# firefly-instrument-controller.net
KiCad netlist of a schematic drawn in EAGLE
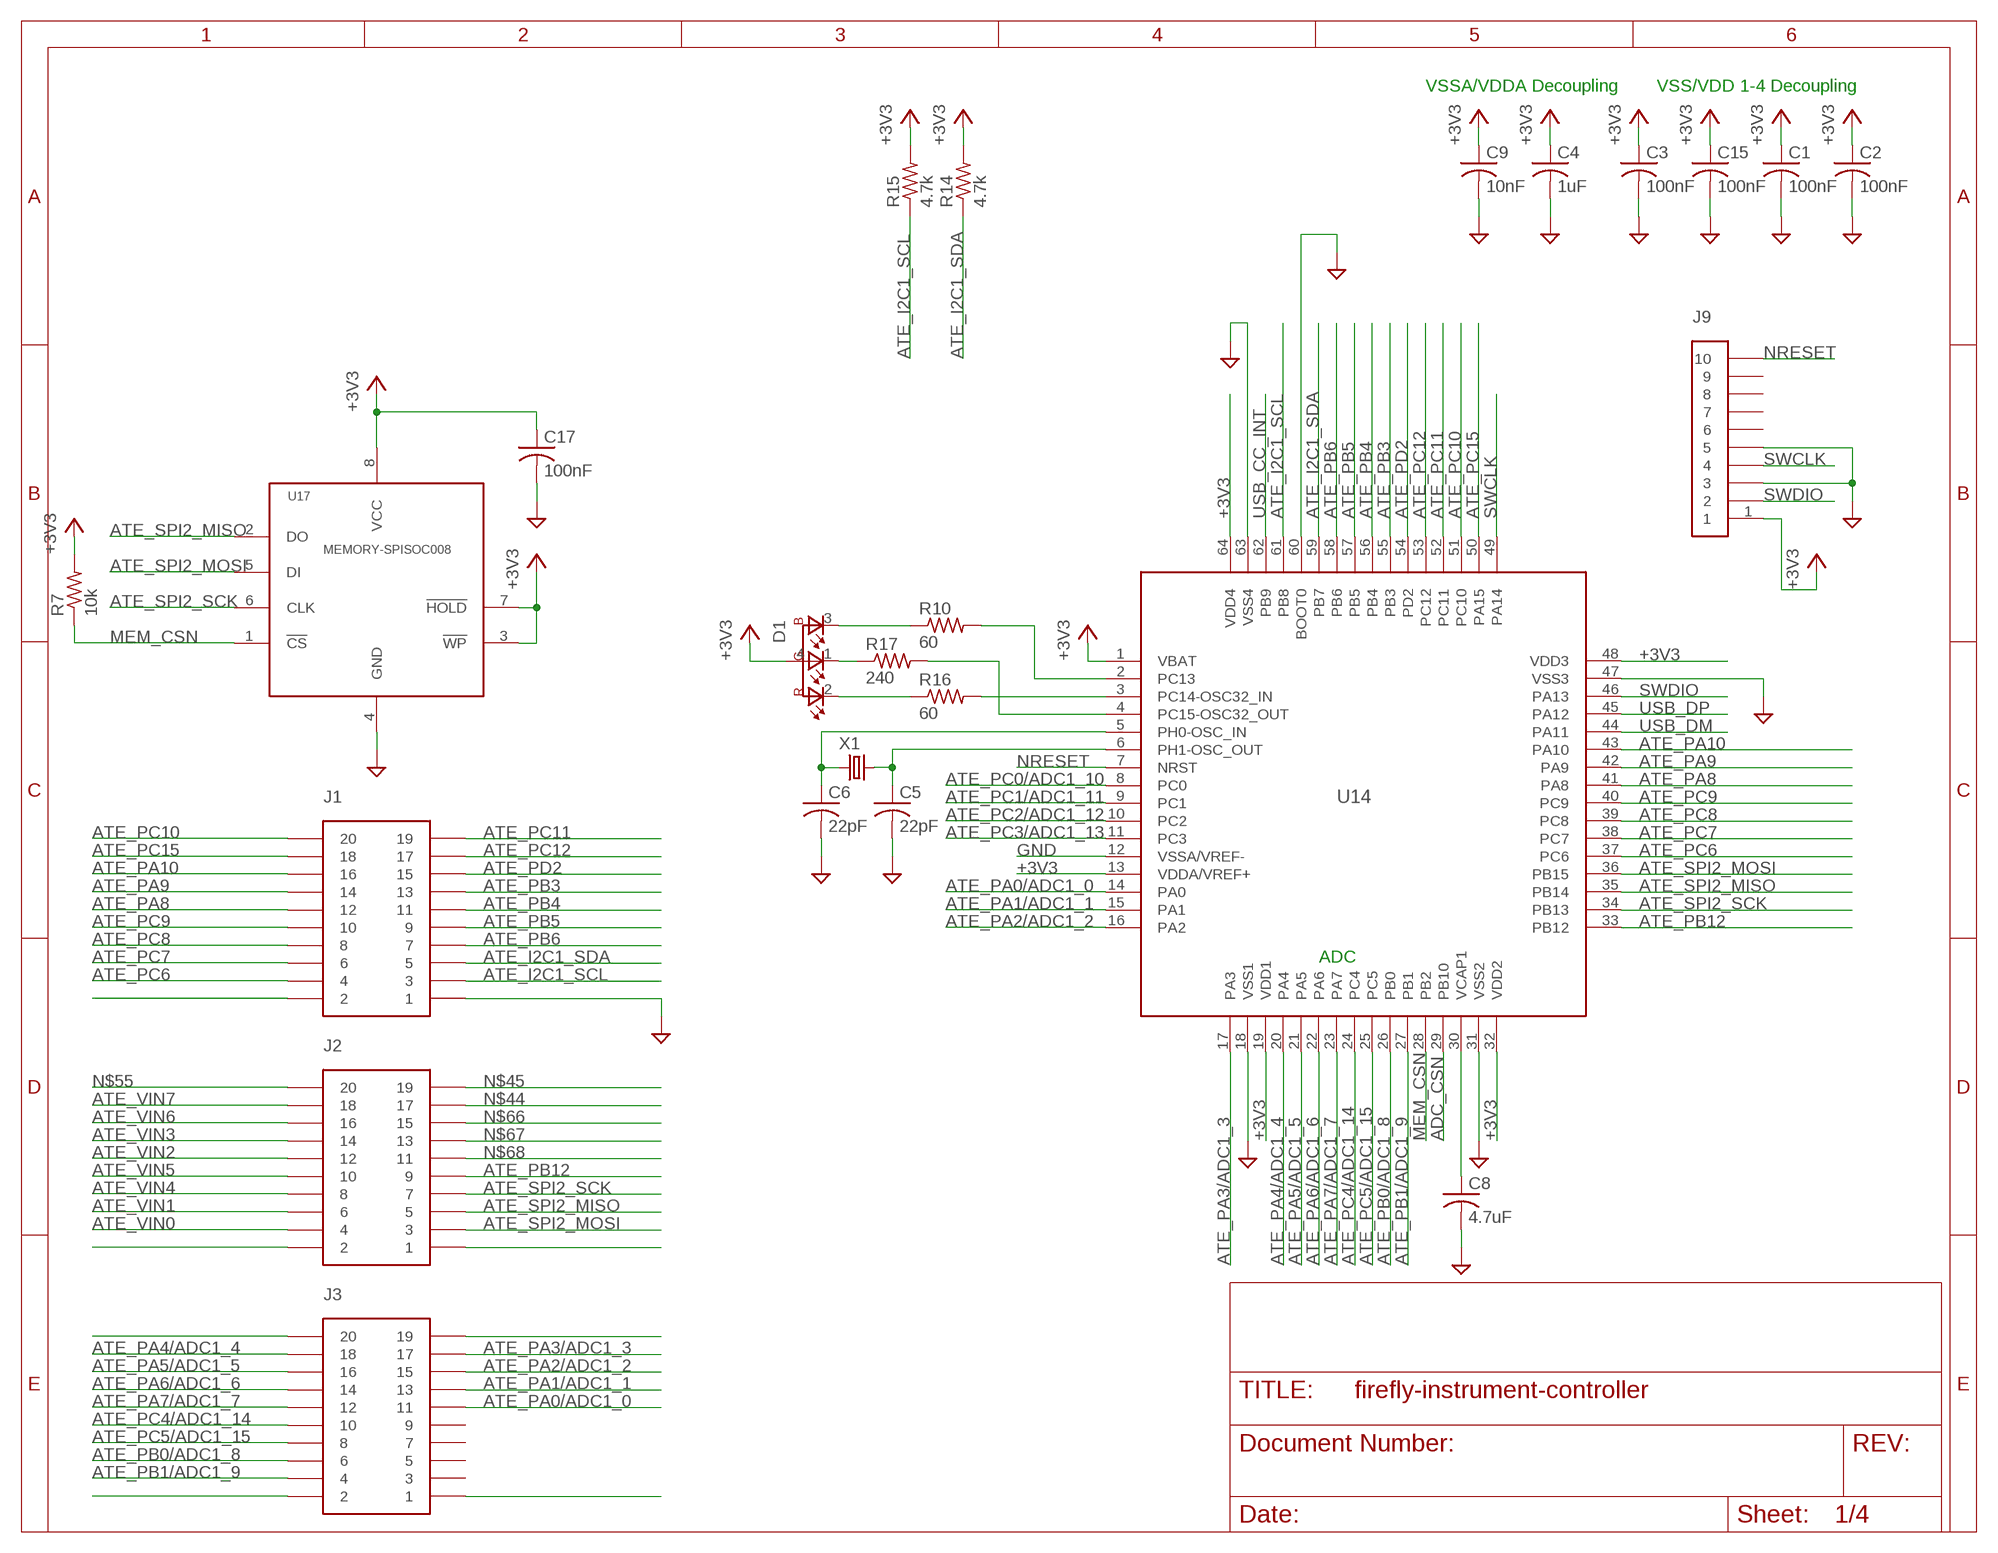
[diagram p0: schematic, sheet 1]
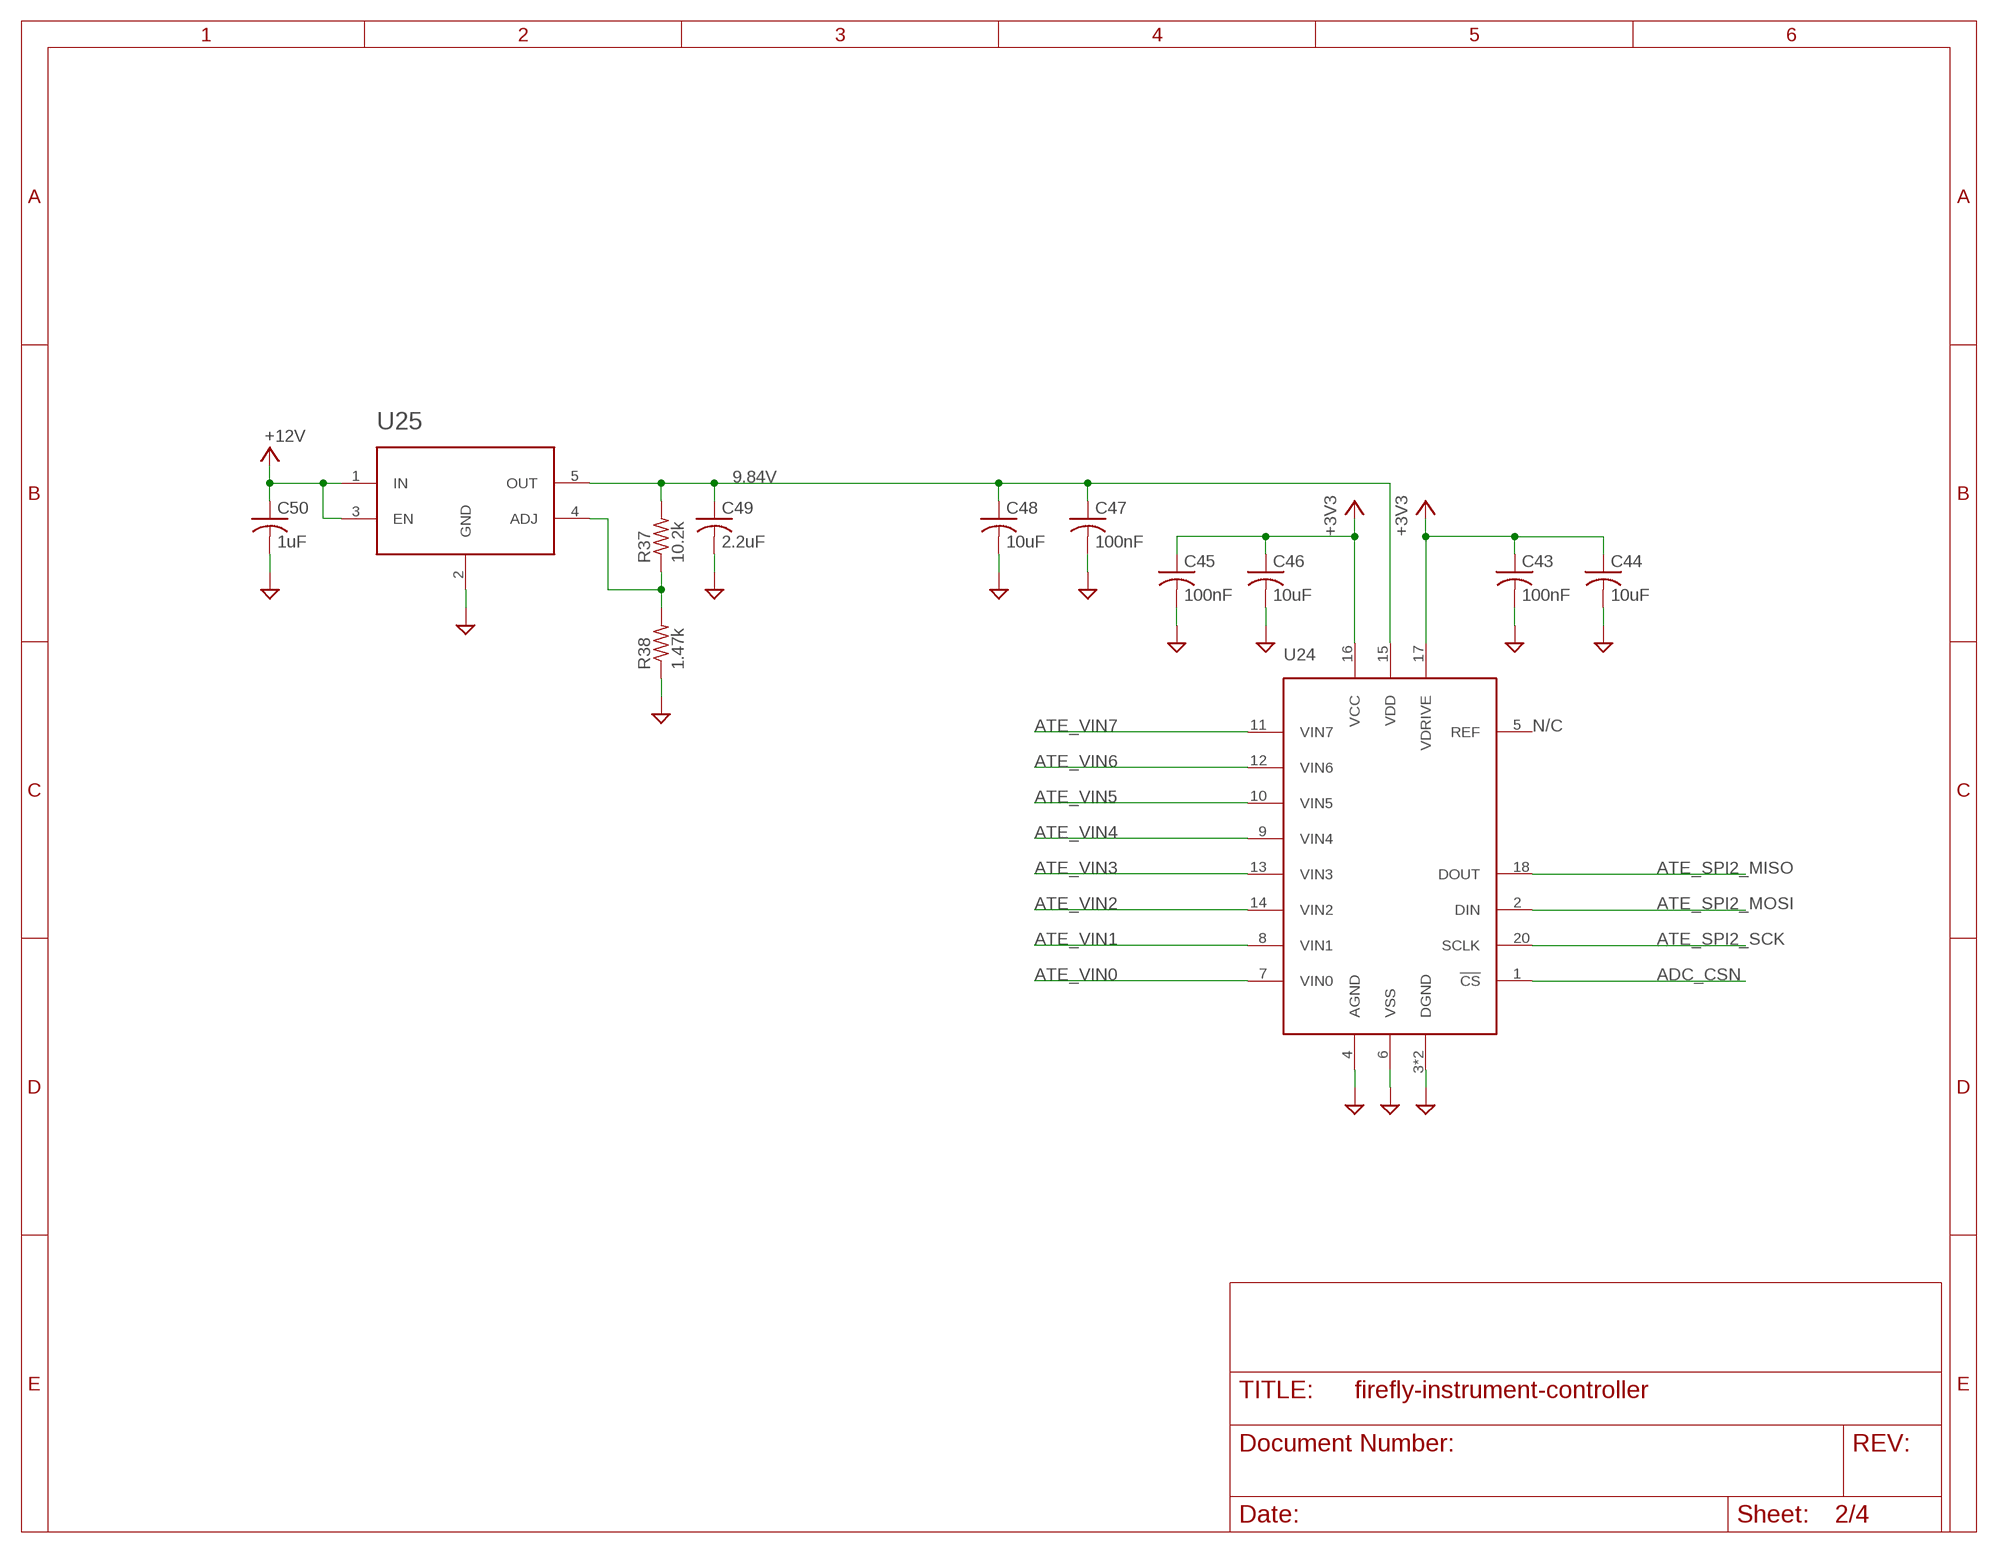
[diagram p1: schematic, sheet 2]
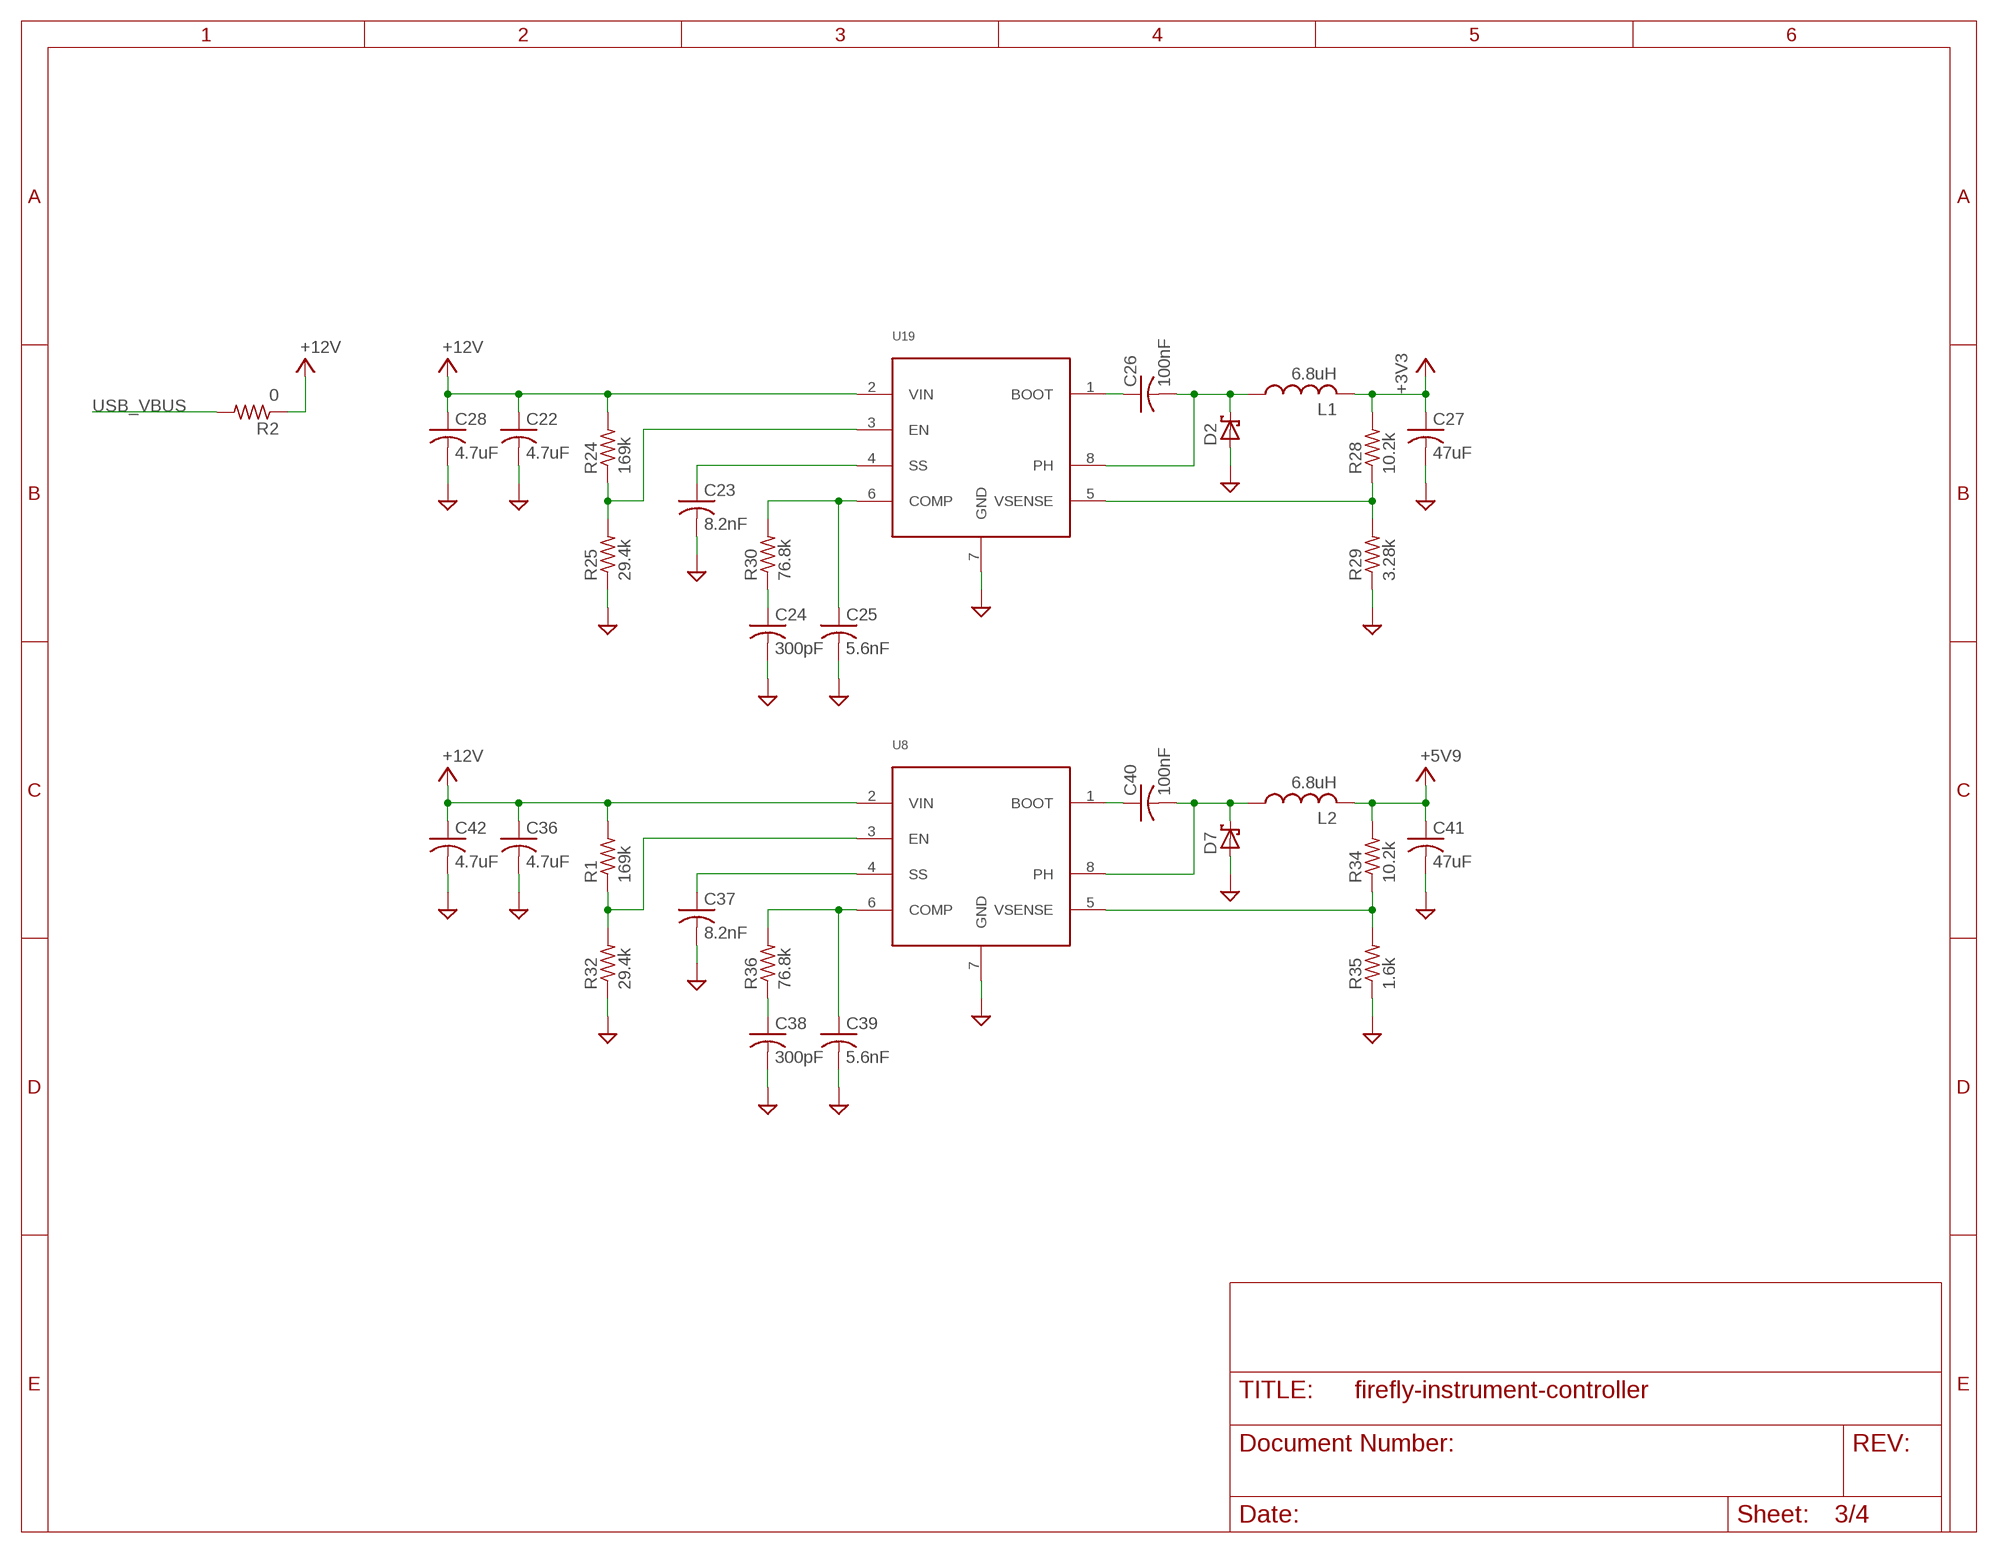
[diagram p2: schematic, sheet 3]
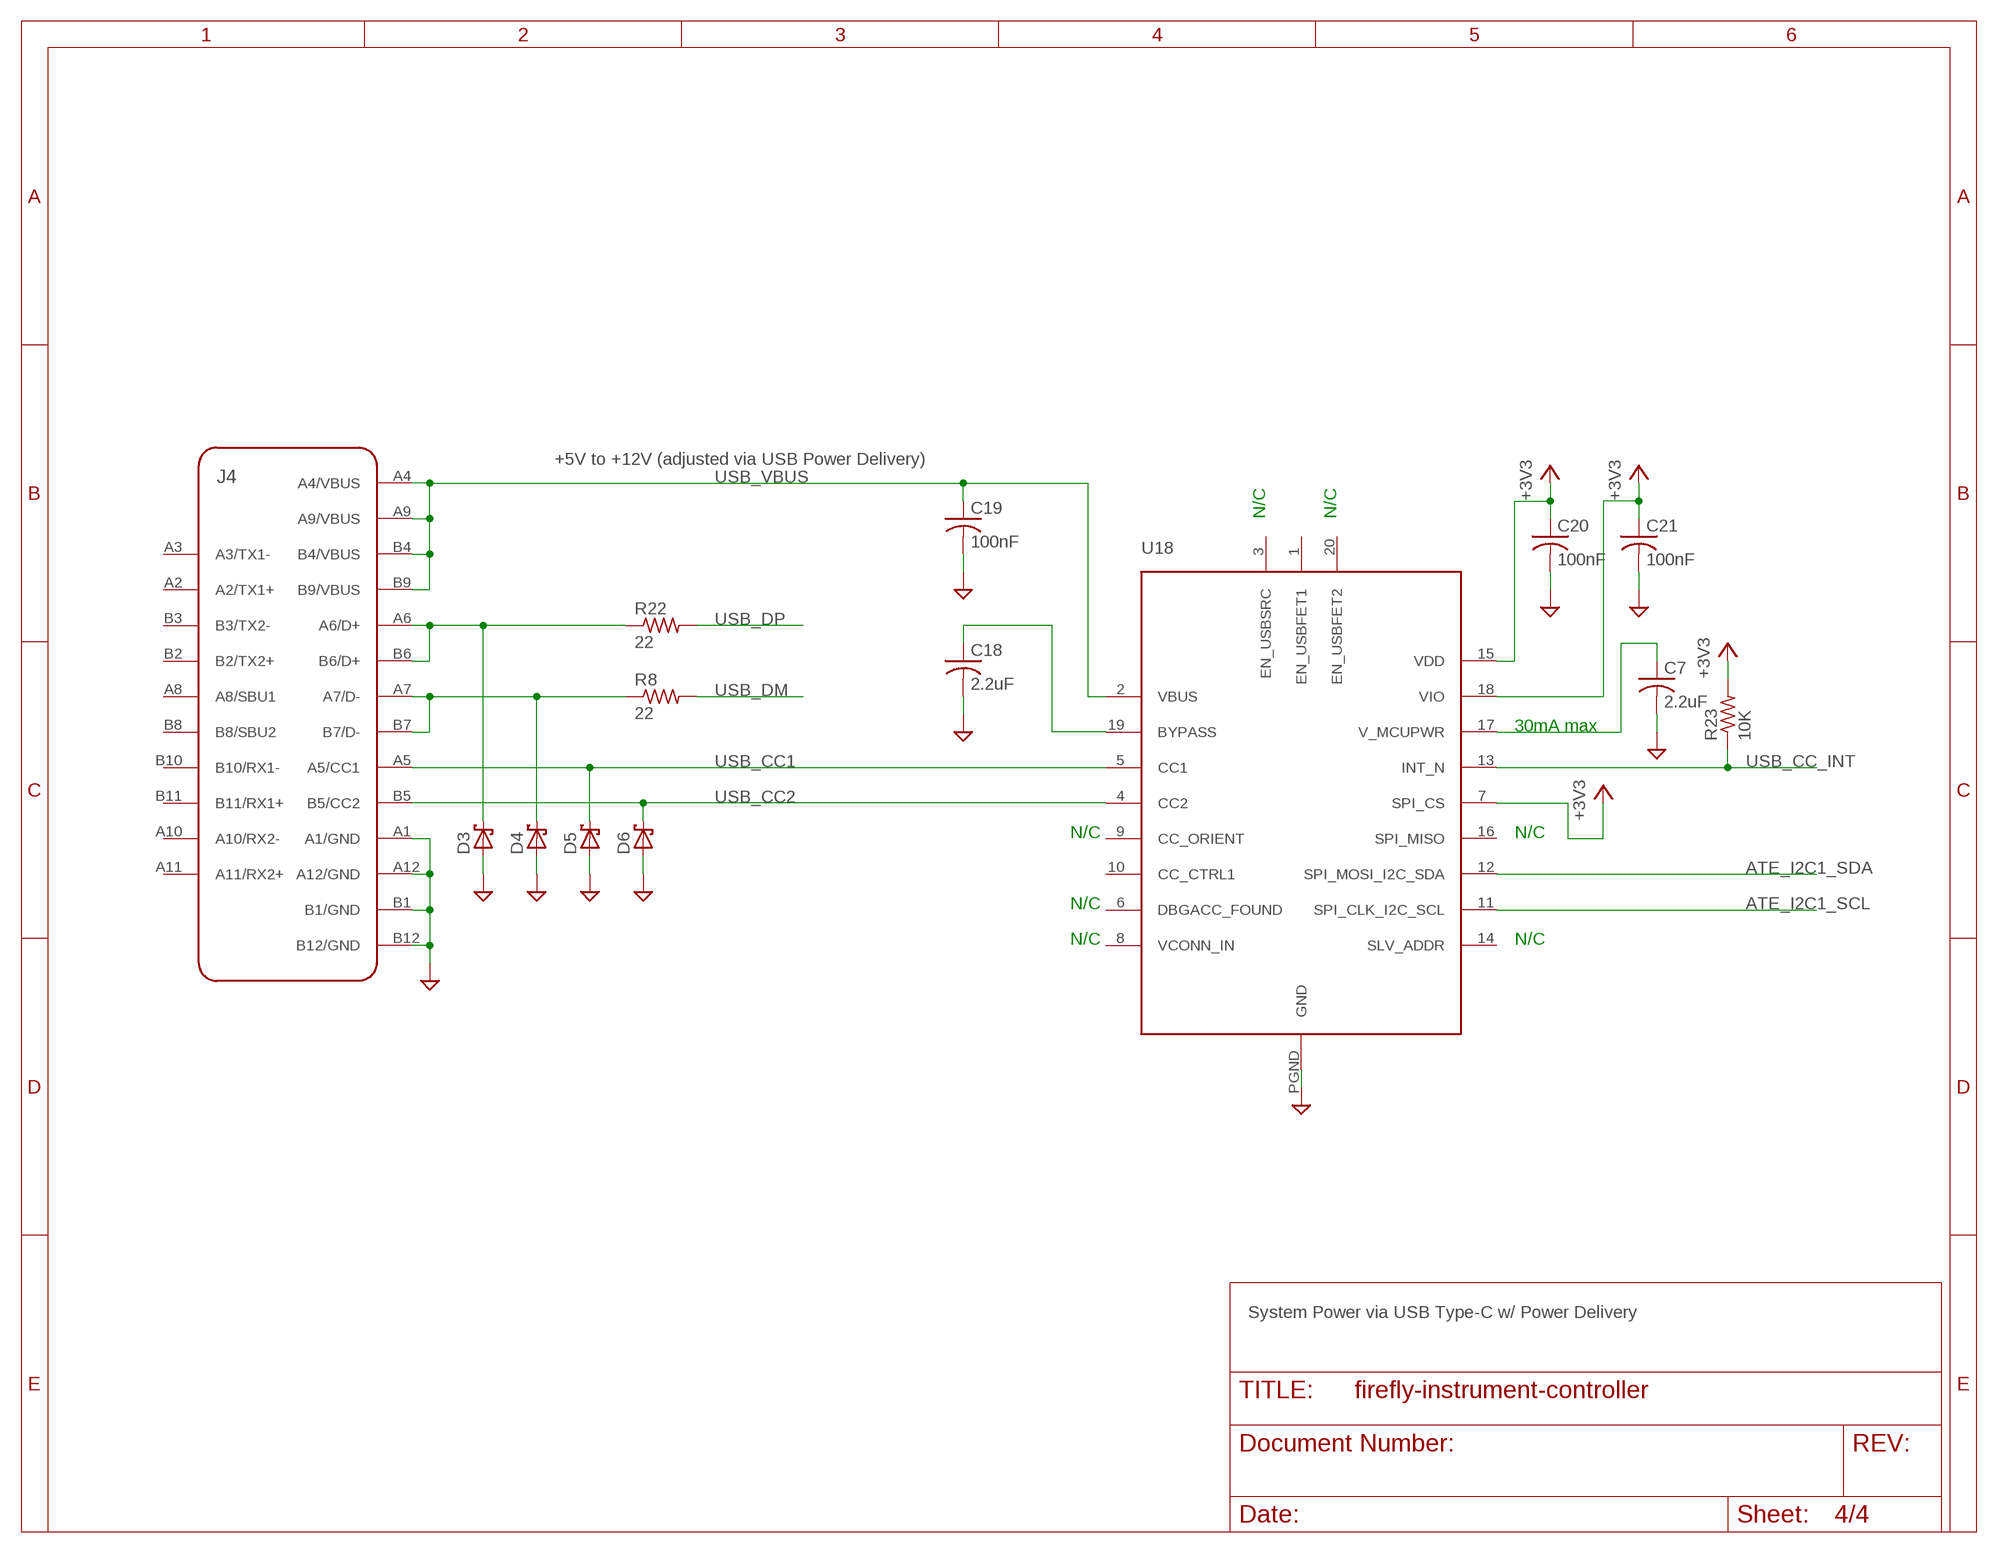
[diagram p3: schematic, sheet 4]

(export (version "E")
  (design (tool "Eeschema 10.0.6"))
  (components
    (comp (ref "C43")
      (value "100nF")
      (footprint "eagle-import:C0805")
      (fields (field (name "MANUFACTURER") "AVX Corporation"))
      (libsource (lib "eagle-import") (part "C-USC0805"))
    )
    (comp (ref "C44")
      (value "10uF")
      (footprint "eagle-import:C0805")
      (fields (field (name "MANUFACTURER") "AVX Corporation"))
      (libsource (lib "eagle-import") (part "C-USC0805"))
    )
    (comp (ref "C45")
      (value "100nF")
      (footprint "eagle-import:C0805")
      (fields (field (name "MANUFACTURER") "AVX Corporation"))
      (libsource (lib "eagle-import") (part "C-USC0805"))
    )
    (comp (ref "C46")
      (value "10uF")
      (footprint "eagle-import:C0805")
      (fields (field (name "MANUFACTURER") "AVX Corporation"))
      (libsource (lib "eagle-import") (part "C-USC0805"))
    )
    (comp (ref "C47")
      (value "100nF")
      (footprint "eagle-import:C0805")
      (fields (field (name "MANUFACTURER") "AVX Corporation"))
      (libsource (lib "eagle-import") (part "C-USC0805"))
    )
    (comp (ref "C48")
      (value "10uF")
      (footprint "eagle-import:C0805")
      (fields (field (name "MANUFACTURER") "AVX Corporation"))
      (libsource (lib "eagle-import") (part "C-USC0805"))
    )
    (comp (ref "C49")
      (value "2.2uF")
      (footprint "eagle-import:C0805")
      (libsource (lib "eagle-import") (part "C-USC0805"))
    )
    (comp (ref "C50")
      (value "1uF")
      (footprint "eagle-import:C0805")
      (fields (field (name "MANUFACTURER") "Samsung Electro-Mechanics America, Inc."))
      (libsource (lib "eagle-import") (part "C-USC0805"))
    )
    (comp (ref "R37")
      (value "10.2k")
      (footprint "eagle-import:R0805")
      (fields (field (name "MANUFACTURER") "Yageo"))
      (libsource (lib "eagle-import") (part "R-USR0805"))
    )
    (comp (ref "R38")
      (value "1.47k")
      (footprint "eagle-import:R0805")
      (fields (field (name "MANUFACTURER") "Yageo"))
      (libsource (lib "eagle-import") (part "R-USR0805"))
    )
    (comp (ref "U24")
      (value "AD7327")
      (footprint "eagle-import:TSSOP-20")
      (libsource (lib "eagle-import") (part "AD7327"))
    )
    (comp (ref "U25")
      (value "VREG-ADJAP2204")
      (footprint "eagle-import:SOT-23-5")
      (fields (field (name "MANUFACTURER") "Diodes Incorporated"))
      (libsource (lib "eagle-import") (part "VREG-ADJAP2204"))
    )
    (comp (ref "C7")
      (value "2.2uF")
      (footprint "eagle-import:C0805")
      (libsource (lib "eagle-import") (part "C-USC0805"))
    )
    (comp (ref "C18")
      (value "2.2uF")
      (footprint "eagle-import:C0805")
      (libsource (lib "eagle-import") (part "C-USC0805"))
    )
    (comp (ref "C19")
      (value "100nF")
      (footprint "eagle-import:C0805")
      (fields (field (name "MANUFACTURER") "AVX Corporation"))
      (libsource (lib "eagle-import") (part "C-USC0805"))
    )
    (comp (ref "C20")
      (value "100nF")
      (footprint "eagle-import:C0805")
      (fields (field (name "MANUFACTURER") "AVX Corporation"))
      (libsource (lib "eagle-import") (part "C-USC0805"))
    )
    (comp (ref "C21")
      (value "100nF")
      (footprint "eagle-import:C0805")
      (fields (field (name "MANUFACTURER") "AVX Corporation"))
      (libsource (lib "eagle-import") (part "C-USC0805"))
    )
    (comp (ref "D3")
      (value "D-USSMM4FXXA")
      (footprint "eagle-import:SMM4FXXA")
      (fields (field (name "MANUFACTURER") "STMicroelectronics"))
      (libsource (lib "eagle-import") (part "D-USSMM4FXXA"))
    )
    (comp (ref "D4")
      (value "D-USSMM4FXXA")
      (footprint "eagle-import:SMM4FXXA")
      (fields (field (name "MANUFACTURER") "STMicroelectronics"))
      (libsource (lib "eagle-import") (part "D-USSMM4FXXA"))
    )
    (comp (ref "D5")
      (value "D-USSMM4FXXA")
      (footprint "eagle-import:SMM4FXXA")
      (fields (field (name "MANUFACTURER") "STMicroelectronics"))
      (libsource (lib "eagle-import") (part "D-USSMM4FXXA"))
    )
    (comp (ref "D6")
      (value "D-USSMM4FXXA")
      (footprint "eagle-import:SMM4FXXA")
      (fields (field (name "MANUFACTURER") "STMicroelectronics"))
      (libsource (lib "eagle-import") (part "D-USSMM4FXXA"))
    )
    (comp (ref "J4")
      (value "USB-CAUSB1-DFN-PTR3")
      (footprint "eagle-import:AUSB1-DFN-PTR3")
      (fields (field (name "MANUFACTURER") "Assmann WSW Components"))
      (libsource (lib "eagle-import") (part "USB-CAUSB1-DFN-PTR3"))
    )
    (comp (ref "R8")
      (value "22")
      (footprint "eagle-import:R0805")
      (fields (field (name "MANUFACTURER") "Yageo"))
      (libsource (lib "eagle-import") (part "R-USR0805"))
    )
    (comp (ref "R22")
      (value "22")
      (footprint "eagle-import:R0805")
      (fields (field (name "MANUFACTURER") "Yageo"))
      (libsource (lib "eagle-import") (part "R-USR0805"))
    )
    (comp (ref "R23")
      (value "10K")
      (footprint "eagle-import:R0805")
      (fields (field (name "MANUFACTURER") "Yageo"))
      (libsource (lib "eagle-import") (part "R-USR0805"))
    )
    (comp (ref "U18")
      (value "PTN5100")
      (footprint "eagle-import:HVQFN20")
      (fields (field (name "MANUFACTURER") "NXP USA Inc."))
      (libsource (lib "eagle-import") (part "PTN5100"))
    )
    (comp (ref "C22")
      (value "4.7uF")
      (footprint "eagle-import:C1210")
      (fields (field (name "MANUFACTURER") "Murata Electronics North America"))
      (libsource (lib "eagle-import") (part "C-USC1210"))
    )
    (comp (ref "C23")
      (value "8.2nF")
      (footprint "eagle-import:C0805")
      (fields (field (name "MANUFACTURER") "Murata Electronics North America"))
      (libsource (lib "eagle-import") (part "C-USC0805"))
    )
    (comp (ref "C24")
      (value "300pF")
      (footprint "eagle-import:C0805")
      (fields (field (name "MANUFACTURER") "Samsung Electro-Mechanics America, Inc."))
      (libsource (lib "eagle-import") (part "C-USC0805"))
    )
    (comp (ref "C25")
      (value "5.6nF")
      (footprint "eagle-import:C0805")
      (fields (field (name "MANUFACTURER") "Yageo"))
      (libsource (lib "eagle-import") (part "C-USC0805"))
    )
    (comp (ref "C26")
      (value "100nF")
      (footprint "eagle-import:C0805")
      (fields (field (name "MANUFACTURER") "AVX Corporation"))
      (libsource (lib "eagle-import") (part "C-USC0805"))
    )
    (comp (ref "C27")
      (value "47uF")
      (footprint "eagle-import:C1206")
      (fields (field (name "MANUFACTURER") "Murata Electronics North America"))
      (libsource (lib "eagle-import") (part "C-USC1206"))
    )
    (comp (ref "C28")
      (value "4.7uF")
      (footprint "eagle-import:C1210")
      (fields (field (name "MANUFACTURER") "Murata Electronics North America"))
      (libsource (lib "eagle-import") (part "C-USC1210"))
    )
    (comp (ref "C36")
      (value "4.7uF")
      (footprint "eagle-import:C1210")
      (fields (field (name "MANUFACTURER") "Murata Electronics North America"))
      (libsource (lib "eagle-import") (part "C-USC1210"))
    )
    (comp (ref "C37")
      (value "8.2nF")
      (footprint "eagle-import:C0805")
      (fields (field (name "MANUFACTURER") "Murata Electronics North America"))
      (libsource (lib "eagle-import") (part "C-USC0805"))
    )
    (comp (ref "C38")
      (value "300pF")
      (footprint "eagle-import:C0805")
      (fields (field (name "MANUFACTURER") "Samsung Electro-Mechanics America, Inc."))
      (libsource (lib "eagle-import") (part "C-USC0805"))
    )
    (comp (ref "C39")
      (value "5.6nF")
      (footprint "eagle-import:C0805")
      (fields (field (name "MANUFACTURER") "Yageo"))
      (libsource (lib "eagle-import") (part "C-USC0805"))
    )
    (comp (ref "C40")
      (value "100nF")
      (footprint "eagle-import:C0805")
      (fields (field (name "MANUFACTURER") "AVX Corporation"))
      (libsource (lib "eagle-import") (part "C-USC0805"))
    )
    (comp (ref "C41")
      (value "47uF")
      (footprint "eagle-import:C1206")
      (fields (field (name "MANUFACTURER") "Murata Electronics North America"))
      (libsource (lib "eagle-import") (part "C-USC1206"))
    )
    (comp (ref "C42")
      (value "4.7uF")
      (footprint "eagle-import:C1210")
      (fields (field (name "MANUFACTURER") "Murata Electronics North America"))
      (libsource (lib "eagle-import") (part "C-USC1210"))
    )
    (comp (ref "D2")
      (value "D-USDO-214AB")
      (footprint "eagle-import:DO-214AB")
      (fields (field (name "MANUFACTURER") "Vishay Semiconductor Diodes Division"))
      (libsource (lib "eagle-import") (part "D-USDO-214AB"))
    )
    (comp (ref "D7")
      (value "D-USDO-214AB")
      (footprint "eagle-import:DO-214AB")
      (fields (field (name "MANUFACTURER") "Vishay Semiconductor Diodes Division"))
      (libsource (lib "eagle-import") (part "D-USDO-214AB"))
    )
    (comp (ref "L1")
      (value "6.8uH")
      (footprint "eagle-import:SDR0805")
      (fields (field (name "MANUFACTURER") "Bourns Inc."))
      (libsource (lib "eagle-import") (part "INDUCTORSDR0805"))
    )
    (comp (ref "L2")
      (value "6.8uH")
      (footprint "eagle-import:SDR0805")
      (fields (field (name "MANUFACTURER") "Bourns Inc."))
      (libsource (lib "eagle-import") (part "INDUCTORSDR0805"))
    )
    (comp (ref "R1")
      (value "169k")
      (footprint "eagle-import:R0805")
      (fields (field (name "MANUFACTURER") "Yageo"))
      (libsource (lib "eagle-import") (part "R-USR0805"))
    )
    (comp (ref "R2")
      (value "0")
      (footprint "eagle-import:R0805")
      (fields (field (name "MANUFACTURER") "Yageo"))
      (libsource (lib "eagle-import") (part "R-USR0805"))
    )
    (comp (ref "R24")
      (value "169k")
      (footprint "eagle-import:R0805")
      (fields (field (name "MANUFACTURER") "Yageo"))
      (libsource (lib "eagle-import") (part "R-USR0805"))
    )
    (comp (ref "R25")
      (value "29.4k")
      (footprint "eagle-import:R0805")
      (fields (field (name "MANUFACTURER") "Yageo"))
      (libsource (lib "eagle-import") (part "R-USR0805"))
    )
    (comp (ref "R28")
      (value "10.2k")
      (footprint "eagle-import:R0805")
      (fields (field (name "MANUFACTURER") "Yageo"))
      (libsource (lib "eagle-import") (part "R-USR0805"))
    )
    (comp (ref "R29")
      (value "3.28k")
      (footprint "eagle-import:R0805")
      (fields (field (name "MANUFACTURER") "Yageo"))
      (libsource (lib "eagle-import") (part "R-USR0805"))
    )
    (comp (ref "R30")
      (value "76.8k")
      (footprint "eagle-import:R0805")
      (fields (field (name "MANUFACTURER") "Yageo"))
      (libsource (lib "eagle-import") (part "R-USR0805"))
    )
    (comp (ref "R32")
      (value "29.4k")
      (footprint "eagle-import:R0805")
      (fields (field (name "MANUFACTURER") "Yageo"))
      (libsource (lib "eagle-import") (part "R-USR0805"))
    )
    (comp (ref "R34")
      (value "10.2k")
      (footprint "eagle-import:R0805")
      (fields (field (name "MANUFACTURER") "Yageo"))
      (libsource (lib "eagle-import") (part "R-USR0805"))
    )
    (comp (ref "R35")
      (value "1.6k")
      (footprint "eagle-import:R0805")
      (fields (field (name "MANUFACTURER") "Yageo"))
      (libsource (lib "eagle-import") (part "R-USR0805"))
    )
    (comp (ref "R36")
      (value "76.8k")
      (footprint "eagle-import:R0805")
      (fields (field (name "MANUFACTURER") "Yageo"))
      (libsource (lib "eagle-import") (part "R-USR0805"))
    )
    (comp (ref "U8")
      (value "TPS54232")
      (footprint "eagle-import:R-PDSO-G8")
      (fields (field (name "MANUFACTURER") "Texas Instruments"))
      (libsource (lib "eagle-import") (part "TPS54232"))
    )
    (comp (ref "U19")
      (value "TPS54232")
      (footprint "eagle-import:R-PDSO-G8")
      (fields (field (name "MANUFACTURER") "Texas Instruments"))
      (libsource (lib "eagle-import") (part "TPS54232"))
    )
    (comp (ref "C1")
      (value "100nF")
      (footprint "eagle-import:C0805")
      (fields (field (name "MANUFACTURER") "AVX Corporation"))
      (libsource (lib "eagle-import") (part "C-USC0805"))
    )
    (comp (ref "C2")
      (value "100nF")
      (footprint "eagle-import:C0805")
      (fields (field (name "MANUFACTURER") "AVX Corporation"))
      (libsource (lib "eagle-import") (part "C-USC0805"))
    )
    (comp (ref "C3")
      (value "100nF")
      (footprint "eagle-import:C0805")
      (fields (field (name "MANUFACTURER") "AVX Corporation"))
      (libsource (lib "eagle-import") (part "C-USC0805"))
    )
    (comp (ref "C4")
      (value "1uF")
      (footprint "eagle-import:C0805")
      (fields (field (name "MANUFACTURER") "Yageo"))
      (libsource (lib "eagle-import") (part "C-USC0805"))
    )
    (comp (ref "C5")
      (value "22pF")
      (footprint "eagle-import:C0805")
      (fields (field (name "MANUFACTURER") "Samsung Electro-Mechanics America, Inc."))
      (libsource (lib "eagle-import") (part "C-USC0805"))
    )
    (comp (ref "C6")
      (value "22pF")
      (footprint "eagle-import:C0805")
      (fields (field (name "MANUFACTURER") "Samsung Electro-Mechanics America, Inc."))
      (libsource (lib "eagle-import") (part "C-USC0805"))
    )
    (comp (ref "C8")
      (value "4.7uF")
      (footprint "eagle-import:C0805")
      (fields (field (name "MANUFACTURER") "Murata Electronics North America"))
      (libsource (lib "eagle-import") (part "C-USC0805"))
    )
    (comp (ref "C9")
      (value "10nF")
      (footprint "eagle-import:C0805")
      (fields (field (name "MANUFACTURER") "AVX Corporation"))
      (libsource (lib "eagle-import") (part "C-USC0805"))
    )
    (comp (ref "C15")
      (value "100nF")
      (footprint "eagle-import:C0805")
      (fields (field (name "MANUFACTURER") "AVX Corporation"))
      (libsource (lib "eagle-import") (part "C-USC0805"))
    )
    (comp (ref "C17")
      (value "100nF")
      (footprint "eagle-import:C0805")
      (fields (field (name "MANUFACTURER") "AVX Corporation"))
      (libsource (lib "eagle-import") (part "C-USC0805"))
    )
    (comp (ref "D1")
      (value "LED-RGB-CAMSL0201RGB")
      (footprint "eagle-import:MSL0201RGB")
      (fields (field (name "MANUFACTURER") "Rohm Semiconductor"))
      (libsource (lib "eagle-import") (part "LED-RGB-CAMSL0201RGB"))
    )
    (comp (ref "J1")
      (value "CON-200.05\"")
      (footprint "eagle-import:CON-HEADER-2X10-0.05")
      (libsource (lib "eagle-import") (part "CON-200.05{dblquote}"))
    )
    (comp (ref "J2")
      (value "CON-200.05\"")
      (footprint "eagle-import:CON-HEADER-2X10-0.05")
      (libsource (lib "eagle-import") (part "CON-200.05{dblquote}"))
    )
    (comp (ref "J3")
      (value "CON-200.05\"")
      (footprint "eagle-import:CON-HEADER-2X10-0.05")
      (libsource (lib "eagle-import") (part "CON-200.05{dblquote}"))
    )
    (comp (ref "J9")
      (value "CON-10SWD")
      (footprint "eagle-import:SWD-10")
      (libsource (lib "eagle-import") (part "CON-10SWD"))
    )
    (comp (ref "R7")
      (value "10k")
      (footprint "eagle-import:R0805")
      (fields (field (name "MANUFACTURER") "Yageo"))
      (libsource (lib "eagle-import") (part "R-USR0805"))
    )
    (comp (ref "R10")
      (value "60")
      (footprint "eagle-import:R0805")
      (fields (field (name "MANUFACTURER") "Yageo"))
      (libsource (lib "eagle-import") (part "R-USR0805"))
    )
    (comp (ref "R14")
      (value "4.7k")
      (footprint "eagle-import:R0805")
      (fields (field (name "MANUFACTURER") "Yageo"))
      (libsource (lib "eagle-import") (part "R-USR0805"))
    )
    (comp (ref "R15")
      (value "4.7k")
      (footprint "eagle-import:R0805")
      (fields (field (name "MANUFACTURER") "Yageo"))
      (libsource (lib "eagle-import") (part "R-USR0805"))
    )
    (comp (ref "R16")
      (value "60")
      (footprint "eagle-import:R0805")
      (fields (field (name "MANUFACTURER") "Yageo"))
      (libsource (lib "eagle-import") (part "R-USR0805"))
    )
    (comp (ref "R17")
      (value "240")
      (footprint "eagle-import:R0805")
      (fields (field (name "MANUFACTURER") "Yageo"))
      (libsource (lib "eagle-import") (part "R-USR0805"))
    )
    (comp (ref "U14")
      (value "STM32F411-LQFP64")
      (footprint "eagle-import:LQFP-64")
      (fields (field (name "MANUFACTURER") "STMicroelectronics"))
      (libsource (lib "eagle-import") (part "STM32F411-LQFP64"))
    )
    (comp (ref "U17")
      (value "MEMORY-SPISOC008")
      (footprint "eagle-import:SOC008")
      (fields (field (name "MANUFACTURER") "Adesto Technologies"))
      (libsource (lib "eagle-import") (part "MEMORY-SPISOC008"))
    )
    (comp (ref "X1")
      (value "XTAL2TXC_7A")
      (footprint "eagle-import:TXC_7A")
      (fields (field (name "MANUFACTURER") "TXC CORPORATION"))
      (libsource (lib "eagle-import") (part "XTAL2TXC_7A"))
    )
  )
  (nets
    (net (code "1") (name "+3V3") (class "Default")
      (node (ref "C1") (pin "1") (pinfunction "1_1") (pintype "passive"))
      (node (ref "C15") (pin "1") (pinfunction "1_1") (pintype "passive"))
      (node (ref "C17") (pin "1") (pinfunction "1_1") (pintype "passive"))
      (node (ref "C2") (pin "1") (pinfunction "1_1") (pintype "passive"))
      (node (ref "C20") (pin "1") (pinfunction "1_1") (pintype "passive"))
      (node (ref "C21") (pin "1") (pinfunction "1_1") (pintype "passive"))
      (node (ref "C27") (pin "1") (pinfunction "1_1") (pintype "passive"))
      (node (ref "C3") (pin "1") (pinfunction "1_1") (pintype "passive"))
      (node (ref "C4") (pin "1") (pinfunction "1_1") (pintype "passive"))
      (node (ref "C43") (pin "1") (pinfunction "1_1") (pintype "passive"))
      (node (ref "C44") (pin "1") (pinfunction "1_1") (pintype "passive"))
      (node (ref "C45") (pin "1") (pinfunction "1_1") (pintype "passive"))
      (node (ref "C46") (pin "1") (pinfunction "1_1") (pintype "passive"))
      (node (ref "C9") (pin "1") (pinfunction "1_1") (pintype "passive"))
      (node (ref "D1") (pin "4") (pinfunction "A_4") (pintype "passive"))
      (node (ref "J9") (pin "1") (pinfunction "1_1") (pintype "bidirectional"))
      (node (ref "L1") (pin "2") (pinfunction "2_2") (pintype "passive"))
      (node (ref "R14") (pin "2") (pinfunction "2_2") (pintype "passive"))
      (node (ref "R15") (pin "2") (pinfunction "2_2") (pintype "passive"))
      (node (ref "R23") (pin "2") (pinfunction "2_2") (pintype "passive"))
      (node (ref "R28") (pin "2") (pinfunction "2_2") (pintype "passive"))
      (node (ref "R7") (pin "2") (pinfunction "2_2") (pintype "passive"))
      (node (ref "U14") (pin "1") (pinfunction "VBAT_1") (pintype "bidirectional"))
      (node (ref "U14") (pin "13") (pinfunction "VDDA/VREF+_13") (pintype "bidirectional"))
      (node (ref "U14") (pin "19") (pinfunction "VDD1_19") (pintype "bidirectional"))
      (node (ref "U14") (pin "32") (pinfunction "VDD2_32") (pintype "bidirectional"))
      (node (ref "U14") (pin "48") (pinfunction "VDD3_48") (pintype "bidirectional"))
      (node (ref "U14") (pin "64") (pinfunction "VDD4_64") (pintype "bidirectional"))
      (node (ref "U17") (pin "3") (pinfunction "~{WP}_3") (pintype "bidirectional"))
      (node (ref "U17") (pin "7") (pinfunction "~{HOLD}_7") (pintype "bidirectional"))
      (node (ref "U17") (pin "8") (pinfunction "VCC_8") (pintype "bidirectional"))
      (node (ref "U18") (pin "15") (pinfunction "VDD_15") (pintype "bidirectional"))
      (node (ref "U18") (pin "18") (pinfunction "VIO_18") (pintype "bidirectional"))
      (node (ref "U18") (pin "7") (pinfunction "SPI_CS_7") (pintype "bidirectional"))
      (node (ref "U24") (pin "16") (pinfunction "VCC_16") (pintype "bidirectional"))
      (node (ref "U24") (pin "17") (pinfunction "VDRIVE_17") (pintype "bidirectional"))
    )
    (net (code "2") (name "+5V9") (class "Default")
      (node (ref "C41") (pin "1") (pinfunction "1_1") (pintype "passive"))
      (node (ref "L2") (pin "2") (pinfunction "2_2") (pintype "passive"))
      (node (ref "R34") (pin "2") (pinfunction "2_2") (pintype "passive"))
    )
    (net (code "3") (name "+12V") (class "Default")
      (node (ref "C22") (pin "1") (pinfunction "1_1") (pintype "passive"))
      (node (ref "C28") (pin "1") (pinfunction "1_1") (pintype "passive"))
      (node (ref "C36") (pin "1") (pinfunction "1_1") (pintype "passive"))
      (node (ref "C42") (pin "1") (pinfunction "1_1") (pintype "passive"))
      (node (ref "C50") (pin "1") (pinfunction "1_1") (pintype "passive"))
      (node (ref "R1") (pin "2") (pinfunction "2_2") (pintype "passive"))
      (node (ref "R2") (pin "1") (pinfunction "1_1") (pintype "passive"))
      (node (ref "R24") (pin "2") (pinfunction "2_2") (pintype "passive"))
      (node (ref "U19") (pin "2") (pinfunction "VIN_2") (pintype "bidirectional"))
      (node (ref "U25") (pin "1") (pinfunction "IN_1") (pintype "bidirectional"))
      (node (ref "U25") (pin "3") (pinfunction "EN_3") (pintype "bidirectional"))
      (node (ref "U8") (pin "2") (pinfunction "VIN_2") (pintype "bidirectional"))
    )
    (net (code "4") (name "ADC_CSN") (class "Default")
      (node (ref "U14") (pin "29") (pinfunction "PB10_29") (pintype "bidirectional"))
      (node (ref "U24") (pin "1") (pinfunction "~{CS}_1") (pintype "bidirectional"))
    )
    (net (code "5") (name "ATE_I2C1_SCL") (class "Default")
      (node (ref "J1") (pin "3") (pinfunction "3_3") (pintype "bidirectional"))
      (node (ref "R15") (pin "1") (pinfunction "1_1") (pintype "passive"))
      (node (ref "U14") (pin "61") (pinfunction "PB8_61") (pintype "bidirectional"))
      (node (ref "U18") (pin "11") (pinfunction "SPI_CLK_I2C_SCL_11") (pintype "bidirectional"))
    )
    (net (code "6") (name "ATE_I2C1_SDA") (class "Default")
      (node (ref "J1") (pin "5") (pinfunction "5_5") (pintype "bidirectional"))
      (node (ref "R14") (pin "1") (pinfunction "1_1") (pintype "passive"))
      (node (ref "U14") (pin "59") (pinfunction "PB7_59") (pintype "bidirectional"))
      (node (ref "U18") (pin "12") (pinfunction "SPI_MOSI_I2C_SDA_12") (pintype "bidirectional"))
    )
    (net (code "7") (name "ATE_PA0{slash}ADC1_0") (class "Default")
      (node (ref "J3") (pin "11") (pinfunction "11_11") (pintype "bidirectional"))
      (node (ref "U14") (pin "14") (pinfunction "PA0_14") (pintype "bidirectional"))
    )
    (net (code "8") (name "ATE_PA1{slash}ADC1_1") (class "Default")
      (node (ref "J3") (pin "13") (pinfunction "13_13") (pintype "bidirectional"))
      (node (ref "U14") (pin "15") (pinfunction "PA1_15") (pintype "bidirectional"))
    )
    (net (code "9") (name "ATE_PA2{slash}ADC1_2") (class "Default")
      (node (ref "J3") (pin "15") (pinfunction "15_15") (pintype "bidirectional"))
      (node (ref "U14") (pin "16") (pinfunction "PA2_16") (pintype "bidirectional"))
    )
    (net (code "10") (name "ATE_PA3{slash}ADC1_3") (class "Default")
      (node (ref "J3") (pin "17") (pinfunction "17_17") (pintype "bidirectional"))
      (node (ref "U14") (pin "17") (pinfunction "PA3_17") (pintype "bidirectional"))
    )
    (net (code "11") (name "ATE_PA4{slash}ADC1_4") (class "Default")
      (node (ref "J3") (pin "18") (pinfunction "18_18") (pintype "bidirectional"))
      (node (ref "U14") (pin "20") (pinfunction "PA4_20") (pintype "bidirectional"))
    )
    (net (code "12") (name "ATE_PA5{slash}ADC1_5") (class "Default")
      (node (ref "J3") (pin "16") (pinfunction "16_16") (pintype "bidirectional"))
      (node (ref "U14") (pin "21") (pinfunction "PA5_21") (pintype "bidirectional"))
    )
    (net (code "13") (name "ATE_PA6{slash}ADC1_6") (class "Default")
      (node (ref "J3") (pin "14") (pinfunction "14_14") (pintype "bidirectional"))
      (node (ref "U14") (pin "22") (pinfunction "PA6_22") (pintype "bidirectional"))
    )
    (net (code "14") (name "ATE_PA7{slash}ADC1_7") (class "Default")
      (node (ref "J3") (pin "12") (pinfunction "12_12") (pintype "bidirectional"))
      (node (ref "U14") (pin "23") (pinfunction "PA7_23") (pintype "bidirectional"))
    )
    (net (code "15") (name "ATE_PA8") (class "Default")
      (node (ref "J1") (pin "12") (pinfunction "12_12") (pintype "bidirectional"))
      (node (ref "U14") (pin "41") (pinfunction "PA8_41") (pintype "bidirectional"))
    )
    (net (code "16") (name "ATE_PA9") (class "Default")
      (node (ref "J1") (pin "14") (pinfunction "14_14") (pintype "bidirectional"))
      (node (ref "U14") (pin "42") (pinfunction "PA9_42") (pintype "bidirectional"))
    )
    (net (code "17") (name "ATE_PA10") (class "Default")
      (node (ref "J1") (pin "16") (pinfunction "16_16") (pintype "bidirectional"))
      (node (ref "U14") (pin "43") (pinfunction "PA10_43") (pintype "bidirectional"))
    )
    (net (code "18") (name "ATE_PB0{slash}ADC1_8") (class "Default")
      (node (ref "J3") (pin "6") (pinfunction "6_6") (pintype "bidirectional"))
      (node (ref "U14") (pin "26") (pinfunction "PB0_26") (pintype "bidirectional"))
    )
    (net (code "19") (name "ATE_PB1{slash}ADC1_9") (class "Default")
      (node (ref "J3") (pin "4") (pinfunction "4_4") (pintype "bidirectional"))
      (node (ref "U14") (pin "27") (pinfunction "PB1_27") (pintype "bidirectional"))
    )
    (net (code "20") (name "ATE_PB3") (class "Default")
      (node (ref "J1") (pin "13") (pinfunction "13_13") (pintype "bidirectional"))
      (node (ref "U14") (pin "55") (pinfunction "PB3_55") (pintype "bidirectional"))
    )
    (net (code "21") (name "ATE_PB4") (class "Default")
      (node (ref "J1") (pin "11") (pinfunction "11_11") (pintype "bidirectional"))
      (node (ref "U14") (pin "56") (pinfunction "PB4_56") (pintype "bidirectional"))
    )
    (net (code "22") (name "ATE_PB5") (class "Default")
      (node (ref "J1") (pin "9") (pinfunction "9_9") (pintype "bidirectional"))
      (node (ref "U14") (pin "57") (pinfunction "PB5_57") (pintype "bidirectional"))
    )
    (net (code "23") (name "ATE_PB6") (class "Default")
      (node (ref "J1") (pin "7") (pinfunction "7_7") (pintype "bidirectional"))
      (node (ref "U14") (pin "58") (pinfunction "PB6_58") (pintype "bidirectional"))
    )
    (net (code "24") (name "ATE_PB12") (class "Default")
      (node (ref "J2") (pin "9") (pinfunction "9_9") (pintype "bidirectional"))
      (node (ref "U14") (pin "33") (pinfunction "PB12_33") (pintype "bidirectional"))
    )
    (net (code "25") (name "ATE_PC0{slash}ADC1_10") (class "Default")
      (node (ref "U14") (pin "8") (pinfunction "PC0_8") (pintype "bidirectional"))
    )
    (net (code "26") (name "ATE_PC1{slash}ADC1_11") (class "Default")
      (node (ref "U14") (pin "9") (pinfunction "PC1_9") (pintype "bidirectional"))
    )
    (net (code "27") (name "ATE_PC2{slash}ADC1_12") (class "Default")
      (node (ref "U14") (pin "10") (pinfunction "PC2_10") (pintype "bidirectional"))
    )
    (net (code "28") (name "ATE_PC3{slash}ADC1_13") (class "Default")
      (node (ref "U14") (pin "11") (pinfunction "PC3_11") (pintype "bidirectional"))
    )
    (net (code "29") (name "ATE_PC4{slash}ADC1_14") (class "Default")
      (node (ref "J3") (pin "10") (pinfunction "10_10") (pintype "bidirectional"))
      (node (ref "U14") (pin "24") (pinfunction "PC4_24") (pintype "bidirectional"))
    )
    (net (code "30") (name "ATE_PC5{slash}ADC1_15") (class "Default")
      (node (ref "J3") (pin "8") (pinfunction "8_8") (pintype "bidirectional"))
      (node (ref "U14") (pin "25") (pinfunction "PC5_25") (pintype "bidirectional"))
    )
    (net (code "31") (name "ATE_PC6") (class "Default")
      (node (ref "J1") (pin "4") (pinfunction "4_4") (pintype "bidirectional"))
      (node (ref "U14") (pin "37") (pinfunction "PC6_37") (pintype "bidirectional"))
    )
    (net (code "32") (name "ATE_PC7") (class "Default")
      (node (ref "J1") (pin "6") (pinfunction "6_6") (pintype "bidirectional"))
      (node (ref "U14") (pin "38") (pinfunction "PC7_38") (pintype "bidirectional"))
    )
    (net (code "33") (name "ATE_PC8") (class "Default")
      (node (ref "J1") (pin "8") (pinfunction "8_8") (pintype "bidirectional"))
      (node (ref "U14") (pin "39") (pinfunction "PC8_39") (pintype "bidirectional"))
    )
    (net (code "34") (name "ATE_PC9") (class "Default")
      (node (ref "J1") (pin "10") (pinfunction "10_10") (pintype "bidirectional"))
      (node (ref "U14") (pin "40") (pinfunction "PC9_40") (pintype "bidirectional"))
    )
    (net (code "35") (name "ATE_PC10") (class "Default")
      (node (ref "J1") (pin "20") (pinfunction "20_20") (pintype "bidirectional"))
      (node (ref "U14") (pin "51") (pinfunction "PC10_51") (pintype "bidirectional"))
    )
    (net (code "36") (name "ATE_PC11") (class "Default")
      (node (ref "J1") (pin "19") (pinfunction "19_19") (pintype "bidirectional"))
      (node (ref "U14") (pin "52") (pinfunction "PC11_52") (pintype "bidirectional"))
    )
    (net (code "37") (name "ATE_PC12") (class "Default")
      (node (ref "J1") (pin "17") (pinfunction "17_17") (pintype "bidirectional"))
      (node (ref "U14") (pin "53") (pinfunction "PC12_53") (pintype "bidirectional"))
    )
    (net (code "38") (name "ATE_PC15") (class "Default")
      (node (ref "J1") (pin "18") (pinfunction "18_18") (pintype "bidirectional"))
      (node (ref "U14") (pin "50") (pinfunction "PA15_50") (pintype "bidirectional"))
    )
    (net (code "39") (name "ATE_PD2") (class "Default")
      (node (ref "J1") (pin "15") (pinfunction "15_15") (pintype "bidirectional"))
      (node (ref "U14") (pin "54") (pinfunction "PD2_54") (pintype "bidirectional"))
    )
    (net (code "40") (name "ATE_SPI2_MISO") (class "Default")
      (node (ref "J2") (pin "5") (pinfunction "5_5") (pintype "bidirectional"))
      (node (ref "U14") (pin "35") (pinfunction "PB14_35") (pintype "bidirectional"))
      (node (ref "U17") (pin "2") (pinfunction "DO_2") (pintype "bidirectional"))
      (node (ref "U24") (pin "18") (pinfunction "DOUT_18") (pintype "bidirectional"))
    )
    (net (code "41") (name "ATE_SPI2_MOSI") (class "Default")
      (node (ref "J2") (pin "3") (pinfunction "3_3") (pintype "bidirectional"))
      (node (ref "U14") (pin "36") (pinfunction "PB15_36") (pintype "bidirectional"))
      (node (ref "U17") (pin "5") (pinfunction "DI_5") (pintype "bidirectional"))
      (node (ref "U24") (pin "2") (pinfunction "DIN_2") (pintype "bidirectional"))
    )
    (net (code "42") (name "ATE_SPI2_SCK") (class "Default")
      (node (ref "J2") (pin "7") (pinfunction "7_7") (pintype "bidirectional"))
      (node (ref "U14") (pin "34") (pinfunction "PB13_34") (pintype "bidirectional"))
      (node (ref "U17") (pin "6") (pinfunction "CLK_6") (pintype "bidirectional"))
      (node (ref "U24") (pin "20") (pinfunction "SCLK_20") (pintype "bidirectional"))
    )
    (net (code "43") (name "ATE_VIN0") (class "Default")
      (node (ref "J2") (pin "4") (pinfunction "4_4") (pintype "bidirectional"))
      (node (ref "U24") (pin "7") (pinfunction "VIN0_7") (pintype "bidirectional"))
    )
    (net (code "44") (name "ATE_VIN1") (class "Default")
      (node (ref "J2") (pin "6") (pinfunction "6_6") (pintype "bidirectional"))
      (node (ref "U24") (pin "8") (pinfunction "VIN1_8") (pintype "bidirectional"))
    )
    (net (code "45") (name "ATE_VIN2") (class "Default")
      (node (ref "J2") (pin "12") (pinfunction "12_12") (pintype "bidirectional"))
      (node (ref "U24") (pin "14") (pinfunction "VIN2_14") (pintype "bidirectional"))
    )
    (net (code "46") (name "ATE_VIN3") (class "Default")
      (node (ref "J2") (pin "14") (pinfunction "14_14") (pintype "bidirectional"))
      (node (ref "U24") (pin "13") (pinfunction "VIN3_13") (pintype "bidirectional"))
    )
    (net (code "47") (name "ATE_VIN4") (class "Default")
      (node (ref "J2") (pin "8") (pinfunction "8_8") (pintype "bidirectional"))
      (node (ref "U24") (pin "9") (pinfunction "VIN4_9") (pintype "bidirectional"))
    )
    (net (code "48") (name "ATE_VIN5") (class "Default")
      (node (ref "J2") (pin "10") (pinfunction "10_10") (pintype "bidirectional"))
      (node (ref "U24") (pin "10") (pinfunction "VIN5_10") (pintype "bidirectional"))
    )
    (net (code "49") (name "ATE_VIN6") (class "Default")
      (node (ref "J2") (pin "16") (pinfunction "16_16") (pintype "bidirectional"))
      (node (ref "U24") (pin "12") (pinfunction "VIN6_12") (pintype "bidirectional"))
    )
    (net (code "50") (name "ATE_VIN7") (class "Default")
      (node (ref "J2") (pin "18") (pinfunction "18_18") (pintype "bidirectional"))
      (node (ref "U24") (pin "11") (pinfunction "VIN7_11") (pintype "bidirectional"))
    )
    (net (code "51") (name "GND") (class "Default")
      (node (ref "C1") (pin "2") (pinfunction "2_2") (pintype "passive"))
      (node (ref "C15") (pin "2") (pinfunction "2_2") (pintype "passive"))
      (node (ref "C17") (pin "2") (pinfunction "2_2") (pintype "passive"))
      (node (ref "C18") (pin "2") (pinfunction "2_2") (pintype "passive"))
      (node (ref "C19") (pin "2") (pinfunction "2_2") (pintype "passive"))
      (node (ref "C2") (pin "2") (pinfunction "2_2") (pintype "passive"))
      (node (ref "C20") (pin "2") (pinfunction "2_2") (pintype "passive"))
      (node (ref "C21") (pin "2") (pinfunction "2_2") (pintype "passive"))
      (node (ref "C22") (pin "2") (pinfunction "2_2") (pintype "passive"))
      (node (ref "C23") (pin "2") (pinfunction "2_2") (pintype "passive"))
      (node (ref "C24") (pin "2") (pinfunction "2_2") (pintype "passive"))
      (node (ref "C25") (pin "2") (pinfunction "2_2") (pintype "passive"))
      (node (ref "C27") (pin "2") (pinfunction "2_2") (pintype "passive"))
      (node (ref "C28") (pin "2") (pinfunction "2_2") (pintype "passive"))
      (node (ref "C3") (pin "2") (pinfunction "2_2") (pintype "passive"))
      (node (ref "C36") (pin "2") (pinfunction "2_2") (pintype "passive"))
      (node (ref "C37") (pin "2") (pinfunction "2_2") (pintype "passive"))
      (node (ref "C38") (pin "2") (pinfunction "2_2") (pintype "passive"))
      (node (ref "C39") (pin "2") (pinfunction "2_2") (pintype "passive"))
      (node (ref "C4") (pin "2") (pinfunction "2_2") (pintype "passive"))
      (node (ref "C41") (pin "2") (pinfunction "2_2") (pintype "passive"))
      (node (ref "C42") (pin "2") (pinfunction "2_2") (pintype "passive"))
      (node (ref "C43") (pin "2") (pinfunction "2_2") (pintype "passive"))
      (node (ref "C44") (pin "2") (pinfunction "2_2") (pintype "passive"))
      (node (ref "C45") (pin "2") (pinfunction "2_2") (pintype "passive"))
      (node (ref "C46") (pin "2") (pinfunction "2_2") (pintype "passive"))
      (node (ref "C47") (pin "2") (pinfunction "2_2") (pintype "passive"))
      (node (ref "C48") (pin "2") (pinfunction "2_2") (pintype "passive"))
      (node (ref "C49") (pin "2") (pinfunction "2_2") (pintype "passive"))
      (node (ref "C5") (pin "2") (pinfunction "2_2") (pintype "passive"))
      (node (ref "C50") (pin "2") (pinfunction "2_2") (pintype "passive"))
      (node (ref "C6") (pin "2") (pinfunction "2_2") (pintype "passive"))
      (node (ref "C7") (pin "2") (pinfunction "2_2") (pintype "passive"))
      (node (ref "C8") (pin "2") (pinfunction "2_2") (pintype "passive"))
      (node (ref "C9") (pin "2") (pinfunction "2_2") (pintype "passive"))
      (node (ref "D2") (pin "A") (pinfunction "A_A") (pintype "passive"))
      (node (ref "D3") (pin "A") (pinfunction "A_A") (pintype "passive"))
      (node (ref "D4") (pin "A") (pinfunction "A_A") (pintype "passive"))
      (node (ref "D5") (pin "A") (pinfunction "A_A") (pintype "passive"))
      (node (ref "D6") (pin "A") (pinfunction "A_A") (pintype "passive"))
      (node (ref "D7") (pin "A") (pinfunction "A_A") (pintype "passive"))
      (node (ref "J1") (pin "1") (pinfunction "1_1") (pintype "bidirectional"))
      (node (ref "J4") (pin "A1") (pinfunction "A1/GND_A1") (pintype "bidirectional"))
      (node (ref "J4") (pin "A12") (pinfunction "A12/GND_A12") (pintype "bidirectional"))
      (node (ref "J4") (pin "B1") (pinfunction "B1/GND_B1") (pintype "bidirectional"))
      (node (ref "J4") (pin "B12") (pinfunction "B12/GND_B12") (pintype "bidirectional"))
      (node (ref "J9") (pin "3") (pinfunction "3_3") (pintype "bidirectional"))
      (node (ref "J9") (pin "5") (pinfunction "5_5") (pintype "bidirectional"))
      (node (ref "R25") (pin "1") (pinfunction "1_1") (pintype "passive"))
      (node (ref "R29") (pin "1") (pinfunction "1_1") (pintype "passive"))
      (node (ref "R32") (pin "1") (pinfunction "1_1") (pintype "passive"))
      (node (ref "R35") (pin "1") (pinfunction "1_1") (pintype "passive"))
      (node (ref "R38") (pin "1") (pinfunction "1_1") (pintype "passive"))
      (node (ref "U14") (pin "12") (pinfunction "VSSA/VREF-_12") (pintype "bidirectional"))
      (node (ref "U14") (pin "18") (pinfunction "VSS1_18") (pintype "bidirectional"))
      (node (ref "U14") (pin "31") (pinfunction "VSS2_31") (pintype "bidirectional"))
      (node (ref "U14") (pin "47") (pinfunction "VSS3_47") (pintype "bidirectional"))
      (node (ref "U14") (pin "60") (pinfunction "BOOT0_60") (pintype "bidirectional"))
      (node (ref "U14") (pin "63") (pinfunction "VSS4_63") (pintype "bidirectional"))
      (node (ref "U17") (pin "4") (pinfunction "GND_4") (pintype "bidirectional"))
      (node (ref "U18") (pin "PGND") (pinfunction "GND_PGND") (pintype "bidirectional"))
      (node (ref "U19") (pin "7") (pinfunction "GND_7") (pintype "bidirectional"))
      (node (ref "U24") (pin "19") (pinfunction "DGND_19") (pintype "bidirectional"))
      (node (ref "U24") (pin "3") (pinfunction "DGND_3") (pintype "bidirectional"))
      (node (ref "U24") (pin "4") (pinfunction "AGND_4") (pintype "bidirectional"))
      (node (ref "U24") (pin "6") (pinfunction "VSS_6") (pintype "bidirectional"))
      (node (ref "U25") (pin "2") (pinfunction "GND_2") (pintype "bidirectional"))
      (node (ref "U8") (pin "7") (pinfunction "GND_7") (pintype "bidirectional"))
    )
    (net (code "52") (name "MEM_CSN") (class "Default")
      (node (ref "R7") (pin "1") (pinfunction "1_1") (pintype "passive"))
      (node (ref "U14") (pin "28") (pinfunction "PB2_28") (pintype "bidirectional"))
      (node (ref "U17") (pin "1") (pinfunction "~{CS}_1") (pintype "bidirectional"))
    )
    (net (code "53") (name "N$44") (class "Default")
      (node (ref "J2") (pin "17") (pinfunction "17_17") (pintype "bidirectional"))
    )
    (net (code "54") (name "N$45") (class "Default")
      (node (ref "J2") (pin "19") (pinfunction "19_19") (pintype "bidirectional"))
    )
    (net (code "55") (name "N$55") (class "Default")
      (node (ref "J2") (pin "20") (pinfunction "20_20") (pintype "bidirectional"))
    )
    (net (code "56") (name "N$66") (class "Default")
      (node (ref "J2") (pin "15") (pinfunction "15_15") (pintype "bidirectional"))
    )
    (net (code "57") (name "N$67") (class "Default")
      (node (ref "J2") (pin "13") (pinfunction "13_13") (pintype "bidirectional"))
    )
    (net (code "58") (name "N$68") (class "Default")
      (node (ref "J2") (pin "11") (pinfunction "11_11") (pintype "bidirectional"))
    )
    (net (code "59") (name "NRESET") (class "Default")
      (node (ref "J9") (pin "10") (pinfunction "10_10") (pintype "bidirectional"))
      (node (ref "U14") (pin "7") (pinfunction "NRST_7") (pintype "bidirectional"))
    )
    (net (code "60") (name "Net-(C24-Pad1)") (class "Default")
      (node (ref "C24") (pin "1") (pinfunction "1_1") (pintype "passive"))
      (node (ref "R30") (pin "1") (pinfunction "1_1") (pintype "passive"))
    )
    (net (code "61") (name "Net-(C38-Pad1)") (class "Default")
      (node (ref "C38") (pin "1") (pinfunction "1_1") (pintype "passive"))
      (node (ref "R36") (pin "1") (pinfunction "1_1") (pintype "passive"))
    )
    (net (code "62") (name "Net-(D1-B)") (class "Default")
      (node (ref "D1") (pin "3") (pinfunction "B_3") (pintype "passive"))
      (node (ref "R10") (pin "1") (pinfunction "1_1") (pintype "passive"))
    )
    (net (code "63") (name "Net-(D1-G)") (class "Default")
      (node (ref "D1") (pin "1") (pinfunction "G_1") (pintype "passive"))
      (node (ref "R17") (pin "1") (pinfunction "1_1") (pintype "passive"))
    )
    (net (code "64") (name "Net-(D1-R)") (class "Default")
      (node (ref "D1") (pin "2") (pinfunction "R_2") (pintype "passive"))
      (node (ref "R16") (pin "1") (pinfunction "1_1") (pintype "passive"))
    )
    (net (code "65") (name "Net-(J4-A6{slash}D+)") (class "Default")
      (node (ref "D3") (pin "C") (pinfunction "C_C") (pintype "passive"))
      (node (ref "J4") (pin "A6") (pinfunction "A6/D+_A6") (pintype "bidirectional"))
      (node (ref "J4") (pin "B6") (pinfunction "B6/D+_B6") (pintype "bidirectional"))
      (node (ref "R22") (pin "1") (pinfunction "1_1") (pintype "passive"))
    )
    (net (code "66") (name "Net-(J4-A7{slash}D-)") (class "Default")
      (node (ref "D4") (pin "C") (pinfunction "C_C") (pintype "passive"))
      (node (ref "J4") (pin "A7") (pinfunction "A7/D-_A7") (pintype "bidirectional"))
      (node (ref "J4") (pin "B7") (pinfunction "B7/D-_B7") (pintype "bidirectional"))
      (node (ref "R8") (pin "1") (pinfunction "1_1") (pintype "passive"))
    )
    (net (code "67") (name "Net-(U8-BOOT)") (class "Default")
      (node (ref "C40") (pin "1") (pinfunction "1_1") (pintype "passive"))
      (node (ref "U8") (pin "1") (pinfunction "BOOT_1") (pintype "bidirectional"))
    )
    (net (code "68") (name "Net-(U8-COMP)") (class "Default")
      (node (ref "C39") (pin "1") (pinfunction "1_1") (pintype "passive"))
      (node (ref "R36") (pin "2") (pinfunction "2_2") (pintype "passive"))
      (node (ref "U8") (pin "6") (pinfunction "COMP_6") (pintype "bidirectional"))
    )
    (net (code "69") (name "Net-(U8-EN)") (class "Default")
      (node (ref "R1") (pin "1") (pinfunction "1_1") (pintype "passive"))
      (node (ref "R32") (pin "2") (pinfunction "2_2") (pintype "passive"))
      (node (ref "U8") (pin "3") (pinfunction "EN_3") (pintype "bidirectional"))
    )
    (net (code "70") (name "Net-(U8-PH)") (class "Default")
      (node (ref "C40") (pin "2") (pinfunction "2_2") (pintype "passive"))
      (node (ref "D7") (pin "C") (pinfunction "C_C") (pintype "passive"))
      (node (ref "L2") (pin "1") (pinfunction "1_1") (pintype "passive"))
      (node (ref "U8") (pin "8") (pinfunction "PH_8") (pintype "bidirectional"))
    )
    (net (code "71") (name "Net-(U8-SS)") (class "Default")
      (node (ref "C37") (pin "1") (pinfunction "1_1") (pintype "passive"))
      (node (ref "U8") (pin "4") (pinfunction "SS_4") (pintype "bidirectional"))
    )
    (net (code "72") (name "Net-(U8-VSENSE)") (class "Default")
      (node (ref "R34") (pin "1") (pinfunction "1_1") (pintype "passive"))
      (node (ref "R35") (pin "2") (pinfunction "2_2") (pintype "passive"))
      (node (ref "U8") (pin "5") (pinfunction "VSENSE_5") (pintype "bidirectional"))
    )
    (net (code "73") (name "Net-(U14-PC13)") (class "Default")
      (node (ref "R10") (pin "2") (pinfunction "2_2") (pintype "passive"))
      (node (ref "U14") (pin "2") (pinfunction "PC13_2") (pintype "bidirectional"))
    )
    (net (code "74") (name "Net-(U14-PC14-OSC32_IN)") (class "Default")
      (node (ref "R16") (pin "2") (pinfunction "2_2") (pintype "passive"))
      (node (ref "U14") (pin "3") (pinfunction "PC14-OSC32_IN_3") (pintype "bidirectional"))
    )
    (net (code "75") (name "Net-(U14-PC15-OSC32_OUT)") (class "Default")
      (node (ref "R17") (pin "2") (pinfunction "2_2") (pintype "passive"))
      (node (ref "U14") (pin "4") (pinfunction "PC15-OSC32_OUT_4") (pintype "bidirectional"))
    )
    (net (code "76") (name "Net-(U14-PH0-OSC_IN)") (class "Default")
      (node (ref "C6") (pin "1") (pinfunction "1_1") (pintype "passive"))
      (node (ref "U14") (pin "5") (pinfunction "PH0-OSC_IN_5") (pintype "bidirectional"))
      (node (ref "X1") (pin "1") (pinfunction "1_1") (pintype "passive"))
    )
    (net (code "77") (name "Net-(U14-PH1-OSC_OUT)") (class "Default")
      (node (ref "C5") (pin "1") (pinfunction "1_1") (pintype "passive"))
      (node (ref "U14") (pin "6") (pinfunction "PH1-OSC_OUT_6") (pintype "bidirectional"))
      (node (ref "X1") (pin "2") (pinfunction "2_2") (pintype "passive"))
    )
    (net (code "78") (name "Net-(U14-VCAP1)") (class "Default")
      (node (ref "C8") (pin "1") (pinfunction "1_1") (pintype "passive"))
      (node (ref "U14") (pin "30") (pinfunction "VCAP1_30") (pintype "bidirectional"))
    )
    (net (code "79") (name "Net-(U18-BYPASS)") (class "Default")
      (node (ref "C18") (pin "1") (pinfunction "1_1") (pintype "passive"))
      (node (ref "U18") (pin "19") (pinfunction "BYPASS_19") (pintype "bidirectional"))
    )
    (net (code "80") (name "Net-(U18-V_MCUPWR)") (class "Default")
      (node (ref "C7") (pin "1") (pinfunction "1_1") (pintype "passive"))
      (node (ref "U18") (pin "17") (pinfunction "V_MCUPWR_17") (pintype "bidirectional"))
    )
    (net (code "81") (name "Net-(U19-BOOT)") (class "Default")
      (node (ref "C26") (pin "1") (pinfunction "1_1") (pintype "passive"))
      (node (ref "U19") (pin "1") (pinfunction "BOOT_1") (pintype "bidirectional"))
    )
    (net (code "82") (name "Net-(U19-COMP)") (class "Default")
      (node (ref "C25") (pin "1") (pinfunction "1_1") (pintype "passive"))
      (node (ref "R30") (pin "2") (pinfunction "2_2") (pintype "passive"))
      (node (ref "U19") (pin "6") (pinfunction "COMP_6") (pintype "bidirectional"))
    )
    (net (code "83") (name "Net-(U19-EN)") (class "Default")
      (node (ref "R24") (pin "1") (pinfunction "1_1") (pintype "passive"))
      (node (ref "R25") (pin "2") (pinfunction "2_2") (pintype "passive"))
      (node (ref "U19") (pin "3") (pinfunction "EN_3") (pintype "bidirectional"))
    )
    (net (code "84") (name "Net-(U19-PH)") (class "Default")
      (node (ref "C26") (pin "2") (pinfunction "2_2") (pintype "passive"))
      (node (ref "D2") (pin "C") (pinfunction "C_C") (pintype "passive"))
      (node (ref "L1") (pin "1") (pinfunction "1_1") (pintype "passive"))
      (node (ref "U19") (pin "8") (pinfunction "PH_8") (pintype "bidirectional"))
    )
    (net (code "85") (name "Net-(U19-SS)") (class "Default")
      (node (ref "C23") (pin "1") (pinfunction "1_1") (pintype "passive"))
      (node (ref "U19") (pin "4") (pinfunction "SS_4") (pintype "bidirectional"))
    )
    (net (code "86") (name "Net-(U19-VSENSE)") (class "Default")
      (node (ref "R28") (pin "1") (pinfunction "1_1") (pintype "passive"))
      (node (ref "R29") (pin "2") (pinfunction "2_2") (pintype "passive"))
      (node (ref "U19") (pin "5") (pinfunction "VSENSE_5") (pintype "bidirectional"))
    )
    (net (code "87") (name "Net-(U24-VDD)") (class "Default")
      (node (ref "C47") (pin "1") (pinfunction "1_1") (pintype "passive"))
      (node (ref "C48") (pin "1") (pinfunction "1_1") (pintype "passive"))
      (node (ref "C49") (pin "1") (pinfunction "1_1") (pintype "passive"))
      (node (ref "R37") (pin "2") (pinfunction "2_2") (pintype "passive"))
      (node (ref "U24") (pin "15") (pinfunction "VDD_15") (pintype "bidirectional"))
      (node (ref "U25") (pin "5") (pinfunction "OUT_5") (pintype "bidirectional"))
    )
    (net (code "88") (name "Net-(U25-ADJ)") (class "Default")
      (node (ref "R37") (pin "1") (pinfunction "1_1") (pintype "passive"))
      (node (ref "R38") (pin "2") (pinfunction "2_2") (pintype "passive"))
      (node (ref "U25") (pin "4") (pinfunction "ADJ_4") (pintype "bidirectional"))
    )
    (net (code "89") (name "SWCLK") (class "Default")
      (node (ref "J9") (pin "4") (pinfunction "4_4") (pintype "bidirectional"))
      (node (ref "U14") (pin "49") (pinfunction "PA14_49") (pintype "bidirectional"))
    )
    (net (code "90") (name "SWDIO") (class "Default")
      (node (ref "J9") (pin "2") (pinfunction "2_2") (pintype "bidirectional"))
      (node (ref "U14") (pin "46") (pinfunction "PA13_46") (pintype "bidirectional"))
    )
    (net (code "91") (name "USB_CC1") (class "Default")
      (node (ref "D5") (pin "C") (pinfunction "C_C") (pintype "passive"))
      (node (ref "J4") (pin "A5") (pinfunction "A5/CC1_A5") (pintype "bidirectional"))
      (node (ref "U18") (pin "5") (pinfunction "CC1_5") (pintype "bidirectional"))
    )
    (net (code "92") (name "USB_CC2") (class "Default")
      (node (ref "D6") (pin "C") (pinfunction "C_C") (pintype "passive"))
      (node (ref "J4") (pin "B5") (pinfunction "B5/CC2_B5") (pintype "bidirectional"))
      (node (ref "U18") (pin "4") (pinfunction "CC2_4") (pintype "bidirectional"))
    )
    (net (code "93") (name "USB_CC_INT") (class "Default")
      (node (ref "R23") (pin "1") (pinfunction "1_1") (pintype "passive"))
      (node (ref "U14") (pin "62") (pinfunction "PB9_62") (pintype "bidirectional"))
      (node (ref "U18") (pin "13") (pinfunction "INT_N_13") (pintype "bidirectional"))
    )
    (net (code "94") (name "USB_DM") (class "Default")
      (node (ref "R8") (pin "2") (pinfunction "2_2") (pintype "passive"))
      (node (ref "U14") (pin "44") (pinfunction "PA11_44") (pintype "bidirectional"))
    )
    (net (code "95") (name "USB_DP") (class "Default")
      (node (ref "R22") (pin "2") (pinfunction "2_2") (pintype "passive"))
      (node (ref "U14") (pin "45") (pinfunction "PA12_45") (pintype "bidirectional"))
    )
    (net (code "96") (name "USB_VBUS") (class "Default")
      (node (ref "C19") (pin "1") (pinfunction "1_1") (pintype "passive"))
      (node (ref "J4") (pin "A4") (pinfunction "A4/VBUS_A4") (pintype "bidirectional"))
      (node (ref "J4") (pin "A9") (pinfunction "A9/VBUS_A9") (pintype "bidirectional"))
      (node (ref "J4") (pin "B4") (pinfunction "B4/VBUS_B4") (pintype "bidirectional"))
      (node (ref "J4") (pin "B9") (pinfunction "B9/VBUS_B9") (pintype "bidirectional"))
      (node (ref "R2") (pin "2") (pinfunction "2_2") (pintype "passive"))
      (node (ref "U18") (pin "2") (pinfunction "VBUS_2") (pintype "bidirectional"))
    )
    (net (code "97") (name "unconnected-(J1-Pad2)") (class "Default")
      (node (ref "J1") (pin "2") (pinfunction "2_2") (pintype "bidirectional"))
    )
    (net (code "98") (name "unconnected-(J2-Pad1)") (class "Default")
      (node (ref "J2") (pin "1") (pinfunction "1_1") (pintype "bidirectional"))
    )
    (net (code "99") (name "unconnected-(J2-Pad2)") (class "Default")
      (node (ref "J2") (pin "2") (pinfunction "2_2") (pintype "bidirectional"))
    )
    (net (code "100") (name "unconnected-(J3-Pad1)") (class "Default")
      (node (ref "J3") (pin "1") (pinfunction "1_1") (pintype "bidirectional"))
    )
    (net (code "101") (name "unconnected-(J3-Pad2)") (class "Default")
      (node (ref "J3") (pin "2") (pinfunction "2_2") (pintype "bidirectional"))
    )
    (net (code "102") (name "unconnected-(J3-Pad3)") (class "Default")
      (node (ref "J3") (pin "3") (pinfunction "3_3") (pintype "bidirectional"))
    )
    (net (code "103") (name "unconnected-(J3-Pad5)") (class "Default")
      (node (ref "J3") (pin "5") (pinfunction "5_5") (pintype "bidirectional"))
    )
    (net (code "104") (name "unconnected-(J3-Pad7)") (class "Default")
      (node (ref "J3") (pin "7") (pinfunction "7_7") (pintype "bidirectional"))
    )
    (net (code "105") (name "unconnected-(J3-Pad9)") (class "Default")
      (node (ref "J3") (pin "9") (pinfunction "9_9") (pintype "bidirectional"))
    )
    (net (code "106") (name "unconnected-(J3-Pad19)") (class "Default")
      (node (ref "J3") (pin "19") (pinfunction "19_19") (pintype "bidirectional"))
    )
    (net (code "107") (name "unconnected-(J3-Pad20)") (class "Default")
      (node (ref "J3") (pin "20") (pinfunction "20_20") (pintype "bidirectional"))
    )
    (net (code "108") (name "unconnected-(J4-A2{slash}TX1+-PadA2)") (class "Default")
      (node (ref "J4") (pin "A2") (pinfunction "A2/TX1+_A2") (pintype "bidirectional"))
    )
    (net (code "109") (name "unconnected-(J4-A3{slash}TX1--PadA3)") (class "Default")
      (node (ref "J4") (pin "A3") (pinfunction "A3/TX1-_A3") (pintype "bidirectional"))
    )
    (net (code "110") (name "unconnected-(J4-A8{slash}SBU1-PadA8)") (class "Default")
      (node (ref "J4") (pin "A8") (pinfunction "A8/SBU1_A8") (pintype "bidirectional"))
    )
    (net (code "111") (name "unconnected-(J4-A10{slash}RX2--PadA10)") (class "Default")
      (node (ref "J4") (pin "A10") (pinfunction "A10/RX2-_A10") (pintype "bidirectional"))
    )
    (net (code "112") (name "unconnected-(J4-A11{slash}RX2+-PadA11)") (class "Default")
      (node (ref "J4") (pin "A11") (pinfunction "A11/RX2+_A11") (pintype "bidirectional"))
    )
    (net (code "113") (name "unconnected-(J4-B2{slash}TX2+-PadB2)") (class "Default")
      (node (ref "J4") (pin "B2") (pinfunction "B2/TX2+_B2") (pintype "bidirectional"))
    )
    (net (code "114") (name "unconnected-(J4-B3{slash}TX2--PadB3)") (class "Default")
      (node (ref "J4") (pin "B3") (pinfunction "B3/TX2-_B3") (pintype "bidirectional"))
    )
    (net (code "115") (name "unconnected-(J4-B8{slash}SBU2-PadB8)") (class "Default")
      (node (ref "J4") (pin "B8") (pinfunction "B8/SBU2_B8") (pintype "bidirectional"))
    )
    (net (code "116") (name "unconnected-(J4-B10{slash}RX1--PadB10)") (class "Default")
      (node (ref "J4") (pin "B10") (pinfunction "B10/RX1-_B10") (pintype "bidirectional"))
    )
    (net (code "117") (name "unconnected-(J4-B11{slash}RX1+-PadB11)") (class "Default")
      (node (ref "J4") (pin "B11") (pinfunction "B11/RX1+_B11") (pintype "bidirectional"))
    )
    (net (code "118") (name "unconnected-(J9-Pad6)") (class "Default")
      (node (ref "J9") (pin "6") (pinfunction "6_6") (pintype "bidirectional"))
    )
    (net (code "119") (name "unconnected-(J9-Pad7)") (class "Default")
      (node (ref "J9") (pin "7") (pinfunction "7_7") (pintype "bidirectional"))
    )
    (net (code "120") (name "unconnected-(J9-Pad8)") (class "Default")
      (node (ref "J9") (pin "8") (pinfunction "8_8") (pintype "bidirectional"))
    )
    (net (code "121") (name "unconnected-(J9-Pad9)") (class "Default")
      (node (ref "J9") (pin "9") (pinfunction "9_9") (pintype "bidirectional"))
    )
    (net (code "122") (name "unconnected-(U18-CC_CTRL1-Pad10)") (class "Default")
      (node (ref "U18") (pin "10") (pinfunction "CC_CTRL1_10") (pintype "bidirectional"))
    )
    (net (code "123") (name "unconnected-(U18-CC_ORIENT-Pad9)") (class "Default")
      (node (ref "U18") (pin "9") (pinfunction "CC_ORIENT_9") (pintype "bidirectional"))
    )
    (net (code "124") (name "unconnected-(U18-DBGACC_FOUND-Pad6)") (class "Default")
      (node (ref "U18") (pin "6") (pinfunction "DBGACC_FOUND_6") (pintype "bidirectional"))
    )
    (net (code "125") (name "unconnected-(U18-EN_USBFET1-Pad1)") (class "Default")
      (node (ref "U18") (pin "1") (pinfunction "EN_USBFET1_1") (pintype "bidirectional"))
    )
    (net (code "126") (name "unconnected-(U18-EN_USBFET2-Pad20)") (class "Default")
      (node (ref "U18") (pin "20") (pinfunction "EN_USBFET2_20") (pintype "bidirectional"))
    )
    (net (code "127") (name "unconnected-(U18-EN_USBSRC-Pad3)") (class "Default")
      (node (ref "U18") (pin "3") (pinfunction "EN_USBSRC_3") (pintype "bidirectional"))
    )
    (net (code "128") (name "unconnected-(U18-SLV_ADDR-Pad14)") (class "Default")
      (node (ref "U18") (pin "14") (pinfunction "SLV_ADDR_14") (pintype "bidirectional"))
    )
    (net (code "129") (name "unconnected-(U18-SPI_MISO-Pad16)") (class "Default")
      (node (ref "U18") (pin "16") (pinfunction "SPI_MISO_16") (pintype "bidirectional"))
    )
    (net (code "130") (name "unconnected-(U18-VCONN_IN-Pad8)") (class "Default")
      (node (ref "U18") (pin "8") (pinfunction "VCONN_IN_8") (pintype "bidirectional"))
    )
    (net (code "131") (name "unconnected-(U24-REF-Pad5)") (class "Default")
      (node (ref "U24") (pin "5") (pinfunction "REF_5") (pintype "bidirectional"))
    )
  )
)
